# Mircod_TEST_LIST_4.net
KiCad netlist of a schematic drawn in Altium Designer
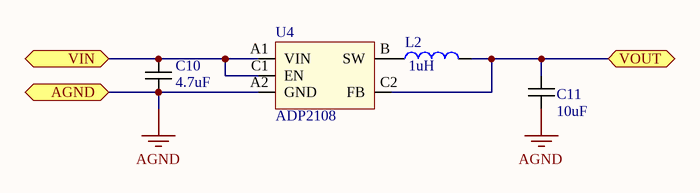
[diagram p0: Mircod_TEST_LIST_4.SchDoc]

(export (version "E")
  (design (tool "Eeschema 10.0.6"))
  (components
    (comp (ref "C10")
      (value "4.7uF")
      (footprint "MIRCOD:CSMD_0603")
      (description "CAPACITOR")
      (libsource (lib "MIRCOD") (part "C_SMD"))
    )
    (comp (ref "C11")
      (value "10uF")
      (footprint "MIRCOD:CSMD_0603")
      (description "CAPACITOR")
      (libsource (lib "MIRCOD") (part "C_SMD"))
    )
    (comp (ref "L2")
      (value "1uH")
      (footprint "MIRCOD:RDSMD_0603")
      (libsource (lib "MIRCOD") (part "INDUCTOR"))
    )
    (comp (ref "U4")
      (value "ADP2108")
      (footprint "MIRCOD:CB-5-3")
      (description "Compact, 600 mA, 3 MHz,  Step-Down DC-to-DC Converter")
      (libsource (lib "MIRCOD") (part "ADP2108"))
    )
  )
  (nets
    (net (code "1") (name "/VIN") (class "Default")
      (node (ref "C10") (pin "2") (pinfunction "2_2") (pintype "passive"))
      (node (ref "U4") (pin "A1") (pinfunction "VIN_A1") (pintype "passive"))
      (node (ref "U4") (pin "C1") (pinfunction "EN_C1") (pintype "passive"))
    )
    (net (code "2") (name "/VOUT") (class "Default")
      (node (ref "C11") (pin "2") (pinfunction "2_2") (pintype "passive"))
      (node (ref "L2") (pin "1") (pinfunction "1_1") (pintype "passive"))
      (node (ref "U4") (pin "C2") (pinfunction "FB_C2") (pintype "passive"))
    )
    (net (code "3") (name "AGND") (class "Default")
      (node (ref "C10") (pin "1") (pinfunction "1_1") (pintype "passive"))
      (node (ref "C11") (pin "1") (pinfunction "1_1") (pintype "passive"))
      (node (ref "U4") (pin "A2") (pinfunction "GND_A2") (pintype "passive"))
    )
    (net (code "4") (name "Net-(U4-SW)") (class "Default")
      (node (ref "L2") (pin "2") (pinfunction "2_2") (pintype "passive"))
      (node (ref "U4") (pin "B") (pinfunction "SW_B") (pintype "passive"))
    )
  )
)
